# UpperBoardAnalogInputs.net
KiCad netlist of a schematic drawn in Altium Designer
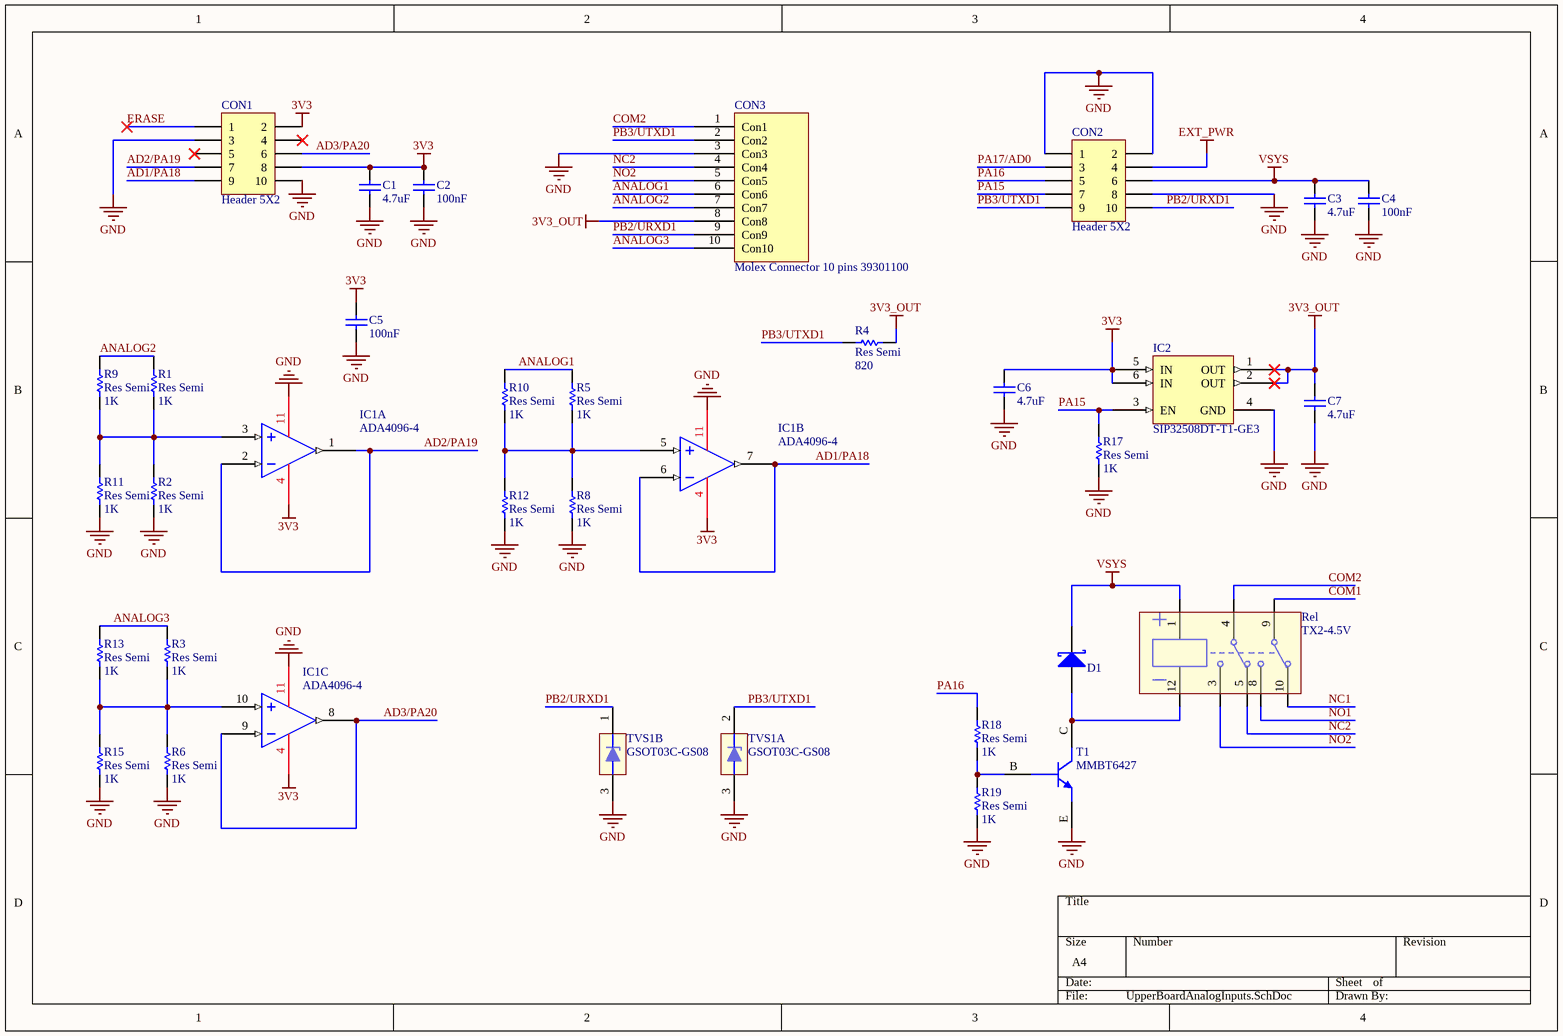
[diagram p0: UpperBoardAnalogInputs.SchDoc]

(export (version "E")
  (design (tool "Eeschema 10.0.6"))
  (components
    (comp (ref "C1")
      (value "4.7uF")
      (footprint "2012[0805]")
      (fields (field (name "VOLTAGE") "6.3V") (field (name "Comment") "Cap1"))
      (libsource (lib "BK4000TGLibraries") (part "Cap1"))
    )
    (comp (ref "C2")
      (value "100nF")
      (footprint "2012[0805]")
      (fields (field (name "VOLTAGE") "6.3V") (field (name "Comment") "Cap1"))
      (libsource (lib "BK4000TGLibraries") (part "Cap1"))
    )
    (comp (ref "C3")
      (value "4.7uF")
      (footprint "2012[0805]")
      (fields (field (name "VOLTAGE") "6.3V") (field (name "Comment") "Cap1"))
      (libsource (lib "BK4000TGLibraries") (part "Cap1"))
    )
    (comp (ref "C4")
      (value "100nF")
      (footprint "2012[0805]")
      (fields (field (name "VOLTAGE") "6.3V") (field (name "Comment") "Cap1"))
      (libsource (lib "BK4000TGLibraries") (part "Cap1"))
    )
    (comp (ref "C5")
      (value "100nF")
      (footprint "2012[0805]")
      (fields (field (name "VOLTAGE") "6.3V") (field (name "Comment") "Cap1"))
      (libsource (lib "BK4000TGLibraries") (part "Cap1"))
    )
    (comp (ref "C6")
      (value "4.7uF")
      (footprint "2012[0805]")
      (fields (field (name "VOLTAGE") "6.3V") (field (name "Comment") "Cap1"))
      (libsource (lib "BK4000TGLibraries") (part "Cap1"))
    )
    (comp (ref "C7")
      (value "4.7uF")
      (footprint "2012[0805]")
      (fields (field (name "VOLTAGE") "6.3V") (field (name "Comment") "Cap1"))
      (libsource (lib "BK4000TGLibraries") (part "Cap1"))
    )
    (comp (ref "CON1")
      (value "Header 5X2")
      (footprint "Header 2x5,1.27mm")
      (description "Header, 5-Pin, Dual row,1.27mm")
      (fields (field (name "PUBLISHER") "Altium Limited"))
      (libsource (lib "BK4000TGLibraries") (part "Header 5X2"))
    )
    (comp (ref "CON2")
      (value "Header 5X2")
      (footprint "Header 2x5,1.27mm")
      (description "Header, 5-Pin, Dual row,1.27mm")
      (fields (field (name "PUBLISHER") "Altium Limited"))
      (libsource (lib "BK4000TGLibraries") (part "Header 5X2"))
    )
    (comp (ref "CON3")
      (value "Molex Connector 10 pins 39301100")
      (footprint "molex 003930-1100")
      (fields (field (name "MANUFACTURER") "MOLEX") (field (name "MANUFACTURER PART NO") "39301100"))
      (libsource (lib "BK4000TGLibraries") (part "Molex Connector 10 pins 39301100"))
    )
    (comp (ref "D1")
      (value "PMEG2005ET")
      (footprint "PMEG2005ET")
      (fields (field (name "MANUFACTURER") "NEXPERIA"))
      (libsource (lib "BK4000TGLibraries") (part "PMEG2005ET"))
    )
    (comp (ref "IC1")
      (value "ADA4096-4")
      (footprint "ADA4096-4")
      (description "30 V, Micropower, Overvoltage Protection,  Rail-to-Rail Input/Output Amplifiers")
      (fields (field (name "MANUFACTURER") "Analog Devices"))
      (libsource (lib "ADA4096-4") (part "ADA4096-4"))
    )
    (comp (ref "IC2")
      (value "SIP32508DT-T1-GE3")
      (footprint "SOT23-6")
      (fields (field (name "MANUFACTURER") "VISHAY"))
      (libsource (lib "BK4000TGLibraries") (part "SIP32508DT-T1-GE3"))
    )
    (comp (ref "R1")
      (value "Res Semi")
      (footprint "2012[0805]")
      (description "Semiconductor Resistor")
      (fields (field (name "ALTIUM_VALUE") "1K") (field (name "PUBLISHER") "Altium Limited"))
      (libsource (lib "Miscellaneous Devices") (part "Res Semi"))
    )
    (comp (ref "R2")
      (value "Res Semi")
      (footprint "2012[0805]")
      (description "Semiconductor Resistor")
      (fields (field (name "ALTIUM_VALUE") "1K") (field (name "PUBLISHER") "Altium Limited"))
      (libsource (lib "Miscellaneous Devices") (part "Res Semi"))
    )
    (comp (ref "R3")
      (value "Res Semi")
      (footprint "2012[0805]")
      (description "Semiconductor Resistor")
      (fields (field (name "ALTIUM_VALUE") "1K") (field (name "PUBLISHER") "Altium Limited"))
      (libsource (lib "Miscellaneous Devices") (part "Res Semi"))
    )
    (comp (ref "R4")
      (value "Res Semi")
      (footprint "2012[0805]")
      (description "Semiconductor Resistor")
      (fields (field (name "ALTIUM_VALUE") "820") (field (name "PUBLISHER") "Altium Limited"))
      (libsource (lib "Miscellaneous Devices") (part "Res Semi"))
    )
    (comp (ref "R5")
      (value "Res Semi")
      (footprint "2012[0805]")
      (description "Semiconductor Resistor")
      (fields (field (name "ALTIUM_VALUE") "1K") (field (name "PUBLISHER") "Altium Limited"))
      (libsource (lib "Miscellaneous Devices") (part "Res Semi"))
    )
    (comp (ref "R6")
      (value "Res Semi")
      (footprint "2012[0805]")
      (description "Semiconductor Resistor")
      (fields (field (name "ALTIUM_VALUE") "1K") (field (name "PUBLISHER") "Altium Limited"))
      (libsource (lib "Miscellaneous Devices") (part "Res Semi"))
    )
    (comp (ref "R8")
      (value "Res Semi")
      (footprint "2012[0805]")
      (description "Semiconductor Resistor")
      (fields (field (name "ALTIUM_VALUE") "1K") (field (name "PUBLISHER") "Altium Limited"))
      (libsource (lib "Miscellaneous Devices") (part "Res Semi"))
    )
    (comp (ref "R9")
      (value "Res Semi")
      (footprint "2012[0805]")
      (description "Semiconductor Resistor")
      (fields (field (name "ALTIUM_VALUE") "1K") (field (name "PUBLISHER") "Altium Limited"))
      (libsource (lib "Miscellaneous Devices") (part "Res Semi"))
    )
    (comp (ref "R10")
      (value "Res Semi")
      (footprint "2012[0805]")
      (description "Semiconductor Resistor")
      (fields (field (name "ALTIUM_VALUE") "1K") (field (name "PUBLISHER") "Altium Limited"))
      (libsource (lib "Miscellaneous Devices") (part "Res Semi"))
    )
    (comp (ref "R11")
      (value "Res Semi")
      (footprint "2012[0805]")
      (description "Semiconductor Resistor")
      (fields (field (name "ALTIUM_VALUE") "1K") (field (name "PUBLISHER") "Altium Limited"))
      (libsource (lib "Miscellaneous Devices") (part "Res Semi"))
    )
    (comp (ref "R12")
      (value "Res Semi")
      (footprint "2012[0805]")
      (description "Semiconductor Resistor")
      (fields (field (name "ALTIUM_VALUE") "1K") (field (name "PUBLISHER") "Altium Limited"))
      (libsource (lib "Miscellaneous Devices") (part "Res Semi"))
    )
    (comp (ref "R13")
      (value "Res Semi")
      (footprint "2012[0805]")
      (description "Semiconductor Resistor")
      (fields (field (name "ALTIUM_VALUE") "1K") (field (name "PUBLISHER") "Altium Limited"))
      (libsource (lib "Miscellaneous Devices") (part "Res Semi"))
    )
    (comp (ref "R15")
      (value "Res Semi")
      (footprint "2012[0805]")
      (description "Semiconductor Resistor")
      (fields (field (name "ALTIUM_VALUE") "1K") (field (name "PUBLISHER") "Altium Limited"))
      (libsource (lib "Miscellaneous Devices") (part "Res Semi"))
    )
    (comp (ref "R17")
      (value "Res Semi")
      (footprint "2012[0805]")
      (description "Semiconductor Resistor")
      (fields (field (name "ALTIUM_VALUE") "1K") (field (name "PUBLISHER") "Altium Limited"))
      (libsource (lib "Miscellaneous Devices") (part "Res Semi"))
    )
    (comp (ref "R18")
      (value "Res Semi")
      (footprint "2012[0805]")
      (description "Semiconductor Resistor")
      (fields (field (name "ALTIUM_VALUE") "1K") (field (name "PUBLISHER") "Altium Limited"))
      (libsource (lib "Miscellaneous Devices") (part "Res Semi"))
    )
    (comp (ref "R19")
      (value "Res Semi")
      (footprint "2012[0805]")
      (description "Semiconductor Resistor")
      (fields (field (name "ALTIUM_VALUE") "1K") (field (name "PUBLISHER") "Altium Limited"))
      (libsource (lib "Miscellaneous Devices") (part "Res Semi"))
    )
    (comp (ref "Rel")
      (value "TX2-4.5V")
      (footprint "Tx4.5 Relay")
      (libsource (lib "BK4000TGAddOnBoard") (part "TX2-4.5V"))
    )
    (comp (ref "T1")
      (value "MMBT6427")
      (footprint "MMBT6427")
      (fields (field (name "MANUFACTURER") "ON SEMICONDUCTOR/FAIRCHILD"))
      (libsource (lib "BK4000TGLibraries") (part "MMBT6427"))
    )
    (comp (ref "TVS1")
      (value "GSOT03C-GS08")
      (footprint "SOT95P245X110-3N")
      (description "Two-Line ESD-Protection in SOT-23")
      (fields (field (name "MANUFACTURER") "Vishay"))
      (libsource (lib "BK4000TGLibraries") (part "GSOT03C-GS08"))
    )
  )
  (nets
    (net (code "1") (name "/AD1{slash}PA18") (class "Default")
      (node (ref "CON1") (pin "9") (pinfunction "9_9") (pintype "passive"))
      (node (ref "IC1") (pin "6") (pinfunction "-INB_6") (pintype "input"))
      (node (ref "IC1") (pin "7") (pinfunction "OUTB_7") (pintype "output"))
    )
    (net (code "2") (name "/AD2{slash}PA19") (class "Default")
      (node (ref "CON1") (pin "7") (pinfunction "7_7") (pintype "passive"))
      (node (ref "IC1") (pin "1") (pinfunction "OUTA_1") (pintype "output"))
      (node (ref "IC1") (pin "2") (pinfunction "-INA_2") (pintype "input"))
    )
    (net (code "3") (name "/AD3{slash}PA20") (class "Default")
      (node (ref "CON1") (pin "6") (pinfunction "6_6") (pintype "passive"))
      (node (ref "IC1") (pin "8") (pinfunction "OUTC_8") (pintype "output"))
      (node (ref "IC1") (pin "9") (pinfunction "-INC_9") (pintype "input"))
    )
    (net (code "4") (name "/ANALOG1") (class "Default")
      (node (ref "CON3") (pin "6") (pinfunction "Con6_6") (pintype "passive"))
      (node (ref "R10") (pin "2") (pinfunction "2_2") (pintype "passive"))
      (node (ref "R5") (pin "2") (pinfunction "2_2") (pintype "passive"))
    )
    (net (code "5") (name "/ANALOG2") (class "Default")
      (node (ref "CON3") (pin "7") (pinfunction "Con7_7") (pintype "passive"))
      (node (ref "R1") (pin "2") (pinfunction "2_2") (pintype "passive"))
      (node (ref "R9") (pin "2") (pinfunction "2_2") (pintype "passive"))
    )
    (net (code "6") (name "/ANALOG3") (class "Default")
      (node (ref "CON3") (pin "10") (pinfunction "Con10_10") (pintype "passive"))
      (node (ref "R13") (pin "2") (pinfunction "2_2") (pintype "passive"))
      (node (ref "R3") (pin "2") (pinfunction "2_2") (pintype "passive"))
    )
    (net (code "7") (name "/COM1") (class "Default")
      (node (ref "Rel") (pin "9") (pinfunction "1_9") (pintype "passive"))
    )
    (net (code "8") (name "/COM2") (class "Default")
      (node (ref "CON3") (pin "1") (pinfunction "Con1_1") (pintype "passive"))
      (node (ref "Rel") (pin "4") (pintype "passive"))
    )
    (net (code "9") (name "/ERASE") (class "Default")
      (node (ref "CON1") (pin "1") (pinfunction "1_1") (pintype "passive+no_connect"))
    )
    (net (code "10") (name "/NC1") (class "Default")
      (node (ref "Rel") (pin "10") (pinfunction "2_10") (pintype "passive"))
    )
    (net (code "11") (name "/NC2") (class "Default")
      (node (ref "CON3") (pin "4") (pinfunction "Con4_4") (pintype "passive"))
      (node (ref "Rel") (pin "5") (pintype "passive"))
    )
    (net (code "12") (name "/NO1") (class "Default")
      (node (ref "Rel") (pin "8") (pinfunction "3_8") (pintype "passive"))
    )
    (net (code "13") (name "/NO2") (class "Default")
      (node (ref "CON3") (pin "5") (pinfunction "Con5_5") (pintype "passive"))
      (node (ref "Rel") (pin "3") (pinfunction "6_3") (pintype "passive"))
    )
    (net (code "14") (name "/PA15") (class "Default")
      (node (ref "CON2") (pin "7") (pinfunction "7_7") (pintype "passive"))
      (node (ref "IC2") (pin "3") (pinfunction "EN_3") (pintype "input"))
      (node (ref "R17") (pin "2") (pinfunction "2_2") (pintype "passive"))
    )
    (net (code "15") (name "/PA16") (class "Default")
      (node (ref "CON2") (pin "5") (pinfunction "5_5") (pintype "passive"))
      (node (ref "R18") (pin "2") (pinfunction "2_2") (pintype "passive"))
    )
    (net (code "16") (name "/PA17{slash}AD0") (class "Default")
      (node (ref "CON2") (pin "3") (pinfunction "3_3") (pintype "passive"))
    )
    (net (code "17") (name "/PB2{slash}URXD1") (class "Default")
      (node (ref "CON2") (pin "10") (pinfunction "10_10") (pintype "passive"))
      (node (ref "CON3") (pin "9") (pinfunction "Con9_9") (pintype "passive"))
      (node (ref "TVS1") (pin "1") (pintype "passive"))
    )
    (net (code "18") (name "/PB3{slash}UTXD1") (class "Default")
      (node (ref "CON2") (pin "9") (pinfunction "9_9") (pintype "passive"))
      (node (ref "CON3") (pin "2") (pinfunction "Con2_2") (pintype "passive"))
      (node (ref "R4") (pin "2") (pinfunction "2_2") (pintype "passive"))
      (node (ref "TVS1") (pin "2") (pintype "passive"))
    )
    (net (code "19") (name "3V3") (class "Default")
      (node (ref "C1") (pin "2") (pinfunction "2_2") (pintype "passive"))
      (node (ref "C2") (pin "2") (pinfunction "2_2") (pintype "passive"))
      (node (ref "C5") (pin "2") (pinfunction "2_2") (pintype "passive"))
      (node (ref "C6") (pin "2") (pinfunction "2_2") (pintype "passive"))
      (node (ref "CON1") (pin "2") (pinfunction "2_2") (pintype "passive"))
      (node (ref "CON1") (pin "8") (pinfunction "8_8") (pintype "passive"))
      (node (ref "IC1") (pin "4") (pinfunction "V+_4") (pintype "passive"))
      (node (ref "IC2") (pin "5") (pinfunction "IN_5") (pintype "input"))
      (node (ref "IC2") (pin "6") (pinfunction "IN_6") (pintype "input"))
    )
    (net (code "20") (name "3V3_OUT") (class "Default")
      (node (ref "C7") (pin "2") (pinfunction "2_2") (pintype "passive"))
      (node (ref "CON3") (pin "8") (pinfunction "Con8_8") (pintype "passive"))
      (node (ref "IC2") (pin "1") (pinfunction "OUT_1") (pintype "output"))
      (node (ref "IC2") (pin "2") (pinfunction "OUT_2") (pintype "output"))
      (node (ref "R4") (pin "1") (pinfunction "1_1") (pintype "passive"))
    )
    (net (code "21") (name "EXT_PWR") (class "Default")
      (node (ref "CON2") (pin "4") (pinfunction "4_4") (pintype "passive"))
    )
    (net (code "22") (name "GND") (class "Default")
      (node (ref "C1") (pin "1") (pinfunction "1_1") (pintype "passive"))
      (node (ref "C2") (pin "1") (pinfunction "1_1") (pintype "passive"))
      (node (ref "C3") (pin "1") (pinfunction "1_1") (pintype "passive"))
      (node (ref "C4") (pin "1") (pinfunction "1_1") (pintype "passive"))
      (node (ref "C5") (pin "1") (pinfunction "1_1") (pintype "passive"))
      (node (ref "C6") (pin "1") (pinfunction "1_1") (pintype "passive"))
      (node (ref "C7") (pin "1") (pinfunction "1_1") (pintype "passive"))
      (node (ref "CON1") (pin "10") (pinfunction "10_10") (pintype "passive"))
      (node (ref "CON1") (pin "3") (pinfunction "3_3") (pintype "passive"))
      (node (ref "CON2") (pin "1") (pinfunction "1_1") (pintype "passive"))
      (node (ref "CON2") (pin "2") (pinfunction "2_2") (pintype "passive"))
      (node (ref "CON2") (pin "8") (pinfunction "8_8") (pintype "passive"))
      (node (ref "CON3") (pin "3") (pinfunction "Con3_3") (pintype "passive"))
      (node (ref "IC1") (pin "11") (pinfunction "V-_11") (pintype "passive"))
      (node (ref "IC2") (pin "4") (pinfunction "GND_4") (pintype "passive"))
      (node (ref "R11") (pin "1") (pinfunction "1_1") (pintype "passive"))
      (node (ref "R12") (pin "1") (pinfunction "1_1") (pintype "passive"))
      (node (ref "R15") (pin "1") (pinfunction "1_1") (pintype "passive"))
      (node (ref "R17") (pin "1") (pinfunction "1_1") (pintype "passive"))
      (node (ref "R19") (pin "1") (pinfunction "1_1") (pintype "passive"))
      (node (ref "R2") (pin "1") (pinfunction "1_1") (pintype "passive"))
      (node (ref "R6") (pin "1") (pinfunction "1_1") (pintype "passive"))
      (node (ref "R8") (pin "1") (pinfunction "1_1") (pintype "passive"))
      (node (ref "T1") (pin "E") (pinfunction "E_E") (pintype "passive"))
      (node (ref "TVS1") (pin "3") (pintype "passive"))
    )
    (net (code "23") (name "Net-(D1-A)") (class "Default")
      (node (ref "D1") (pin "1") (pinfunction "A_1") (pintype "passive"))
      (node (ref "Rel") (pin "12") (pintype "passive"))
      (node (ref "T1") (pin "C") (pinfunction "C_C") (pintype "passive"))
    )
    (net (code "24") (name "Net-(IC1A-+INA)") (class "Default")
      (node (ref "IC1") (pin "3") (pinfunction "+INA_3") (pintype "input"))
      (node (ref "R1") (pin "1") (pinfunction "1_1") (pintype "passive"))
      (node (ref "R11") (pin "2") (pinfunction "2_2") (pintype "passive"))
      (node (ref "R2") (pin "2") (pinfunction "2_2") (pintype "passive"))
      (node (ref "R9") (pin "1") (pinfunction "1_1") (pintype "passive"))
    )
    (net (code "25") (name "Net-(IC1B-+INB)") (class "Default")
      (node (ref "IC1") (pin "5") (pinfunction "+INB_5") (pintype "input"))
      (node (ref "R10") (pin "1") (pinfunction "1_1") (pintype "passive"))
      (node (ref "R12") (pin "2") (pinfunction "2_2") (pintype "passive"))
      (node (ref "R5") (pin "1") (pinfunction "1_1") (pintype "passive"))
      (node (ref "R8") (pin "2") (pinfunction "2_2") (pintype "passive"))
    )
    (net (code "26") (name "Net-(IC1C-+INC)") (class "Default")
      (node (ref "IC1") (pin "10") (pinfunction "+INC_10") (pintype "input"))
      (node (ref "R13") (pin "1") (pinfunction "1_1") (pintype "passive"))
      (node (ref "R15") (pin "2") (pinfunction "2_2") (pintype "passive"))
      (node (ref "R3") (pin "1") (pinfunction "1_1") (pintype "passive"))
      (node (ref "R6") (pin "2") (pinfunction "2_2") (pintype "passive"))
    )
    (net (code "27") (name "Net-(R18-Pad1)") (class "Default")
      (node (ref "R18") (pin "1") (pinfunction "1_1") (pintype "passive"))
      (node (ref "R19") (pin "2") (pinfunction "2_2") (pintype "passive"))
      (node (ref "T1") (pin "B") (pinfunction "B_B") (pintype "passive"))
    )
    (net (code "28") (name "VSYS") (class "Default")
      (node (ref "C3") (pin "2") (pinfunction "2_2") (pintype "passive"))
      (node (ref "C4") (pin "2") (pinfunction "2_2") (pintype "passive"))
      (node (ref "CON2") (pin "6") (pinfunction "6_6") (pintype "passive"))
      (node (ref "D1") (pin "3") (pinfunction "K_3") (pintype "passive"))
      (node (ref "Rel") (pin "1") (pintype "passive"))
    )
    (net (code "29") (name "unconnected-(CON1-Pad4)") (class "Default")
      (node (ref "CON1") (pin "4") (pinfunction "4_4") (pintype "passive+no_connect"))
    )
    (net (code "30") (name "unconnected-(CON1-Pad5)") (class "Default")
      (node (ref "CON1") (pin "5") (pinfunction "5_5") (pintype "passive+no_connect"))
    )
  )
)
